# Grove_-_Tilt_Switch_v1_1.net
KiCad netlist of a schematic drawn in EAGLE
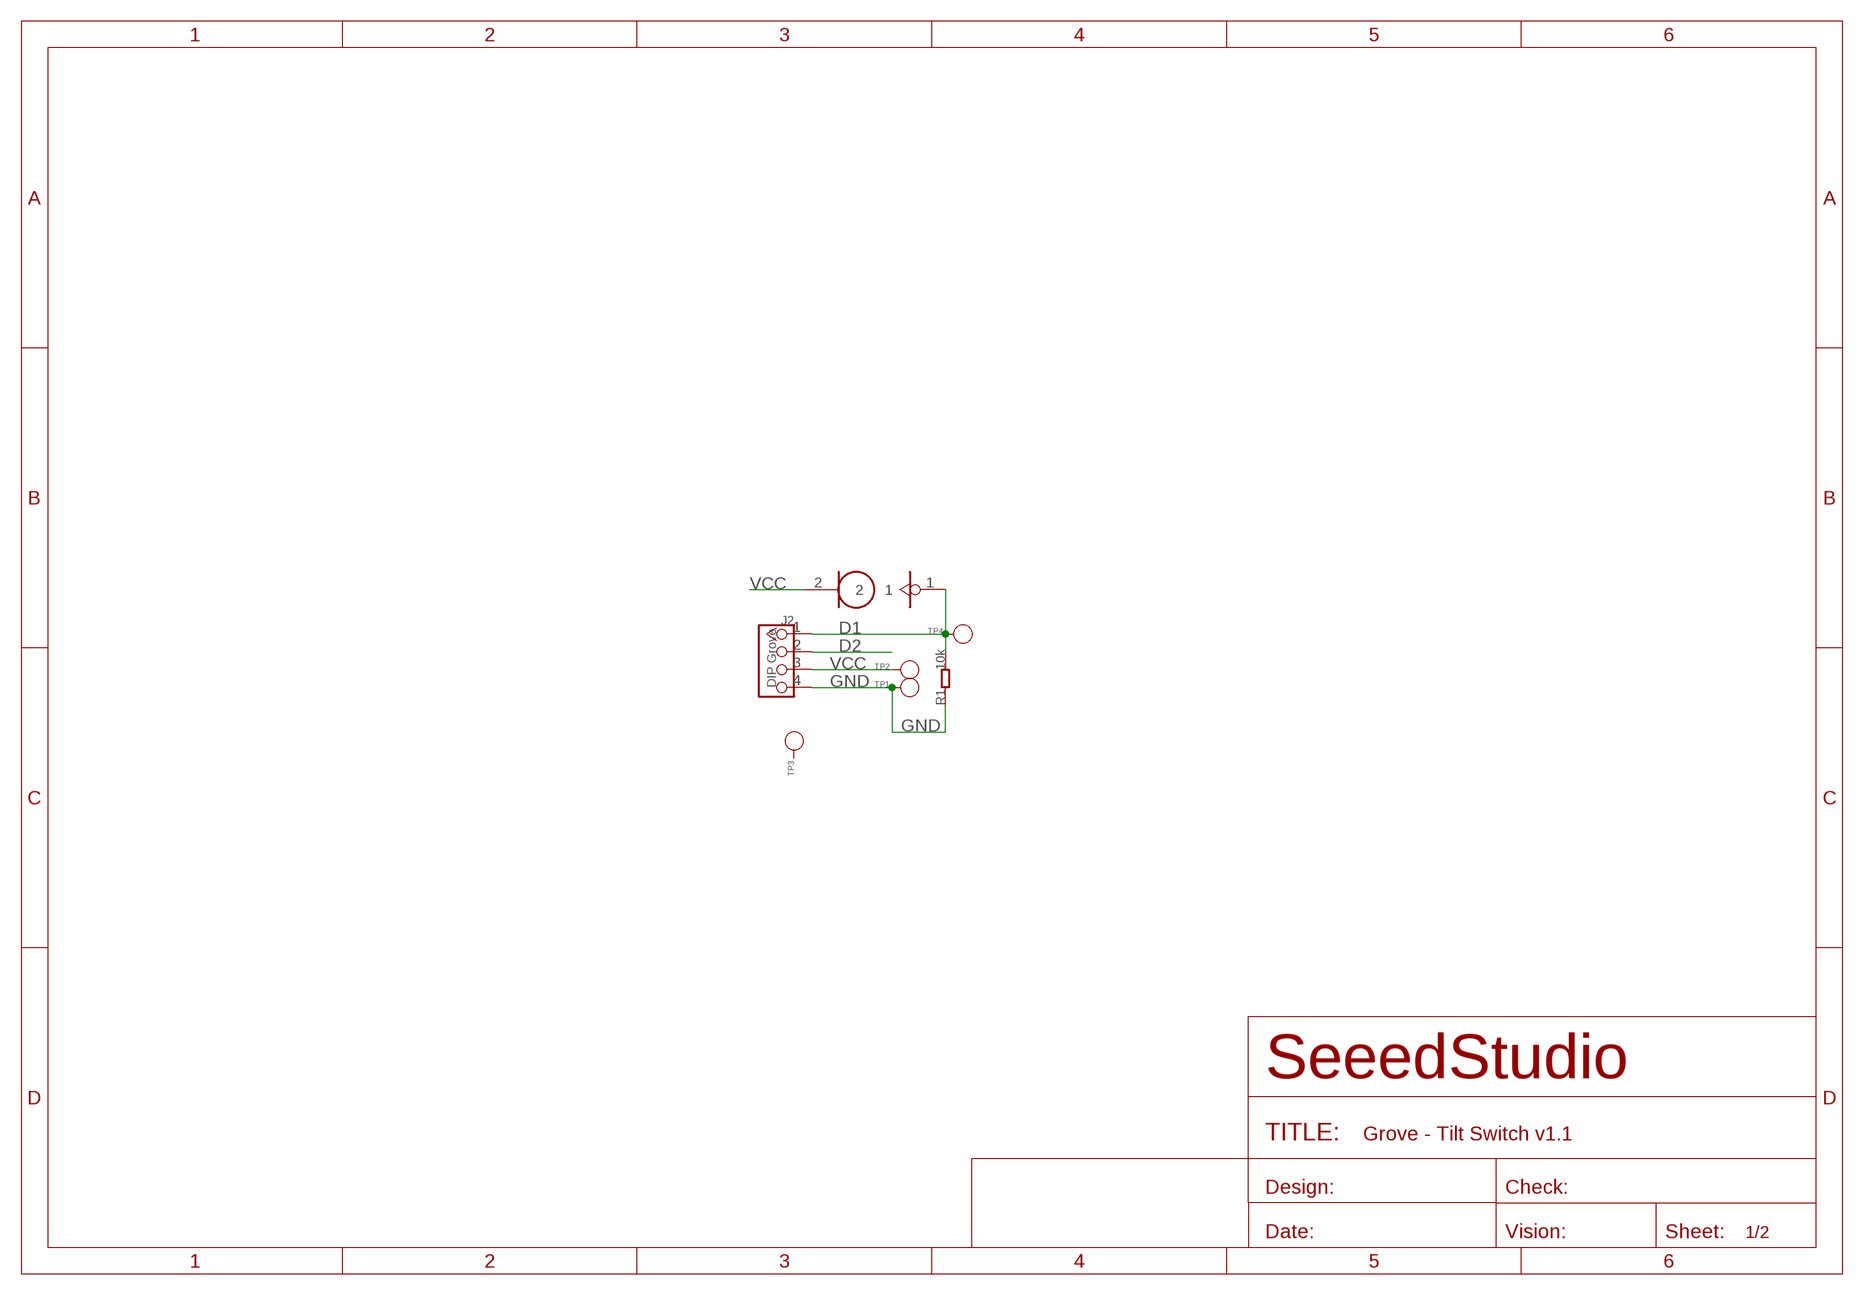
[diagram p0: schematic, sheet 1]
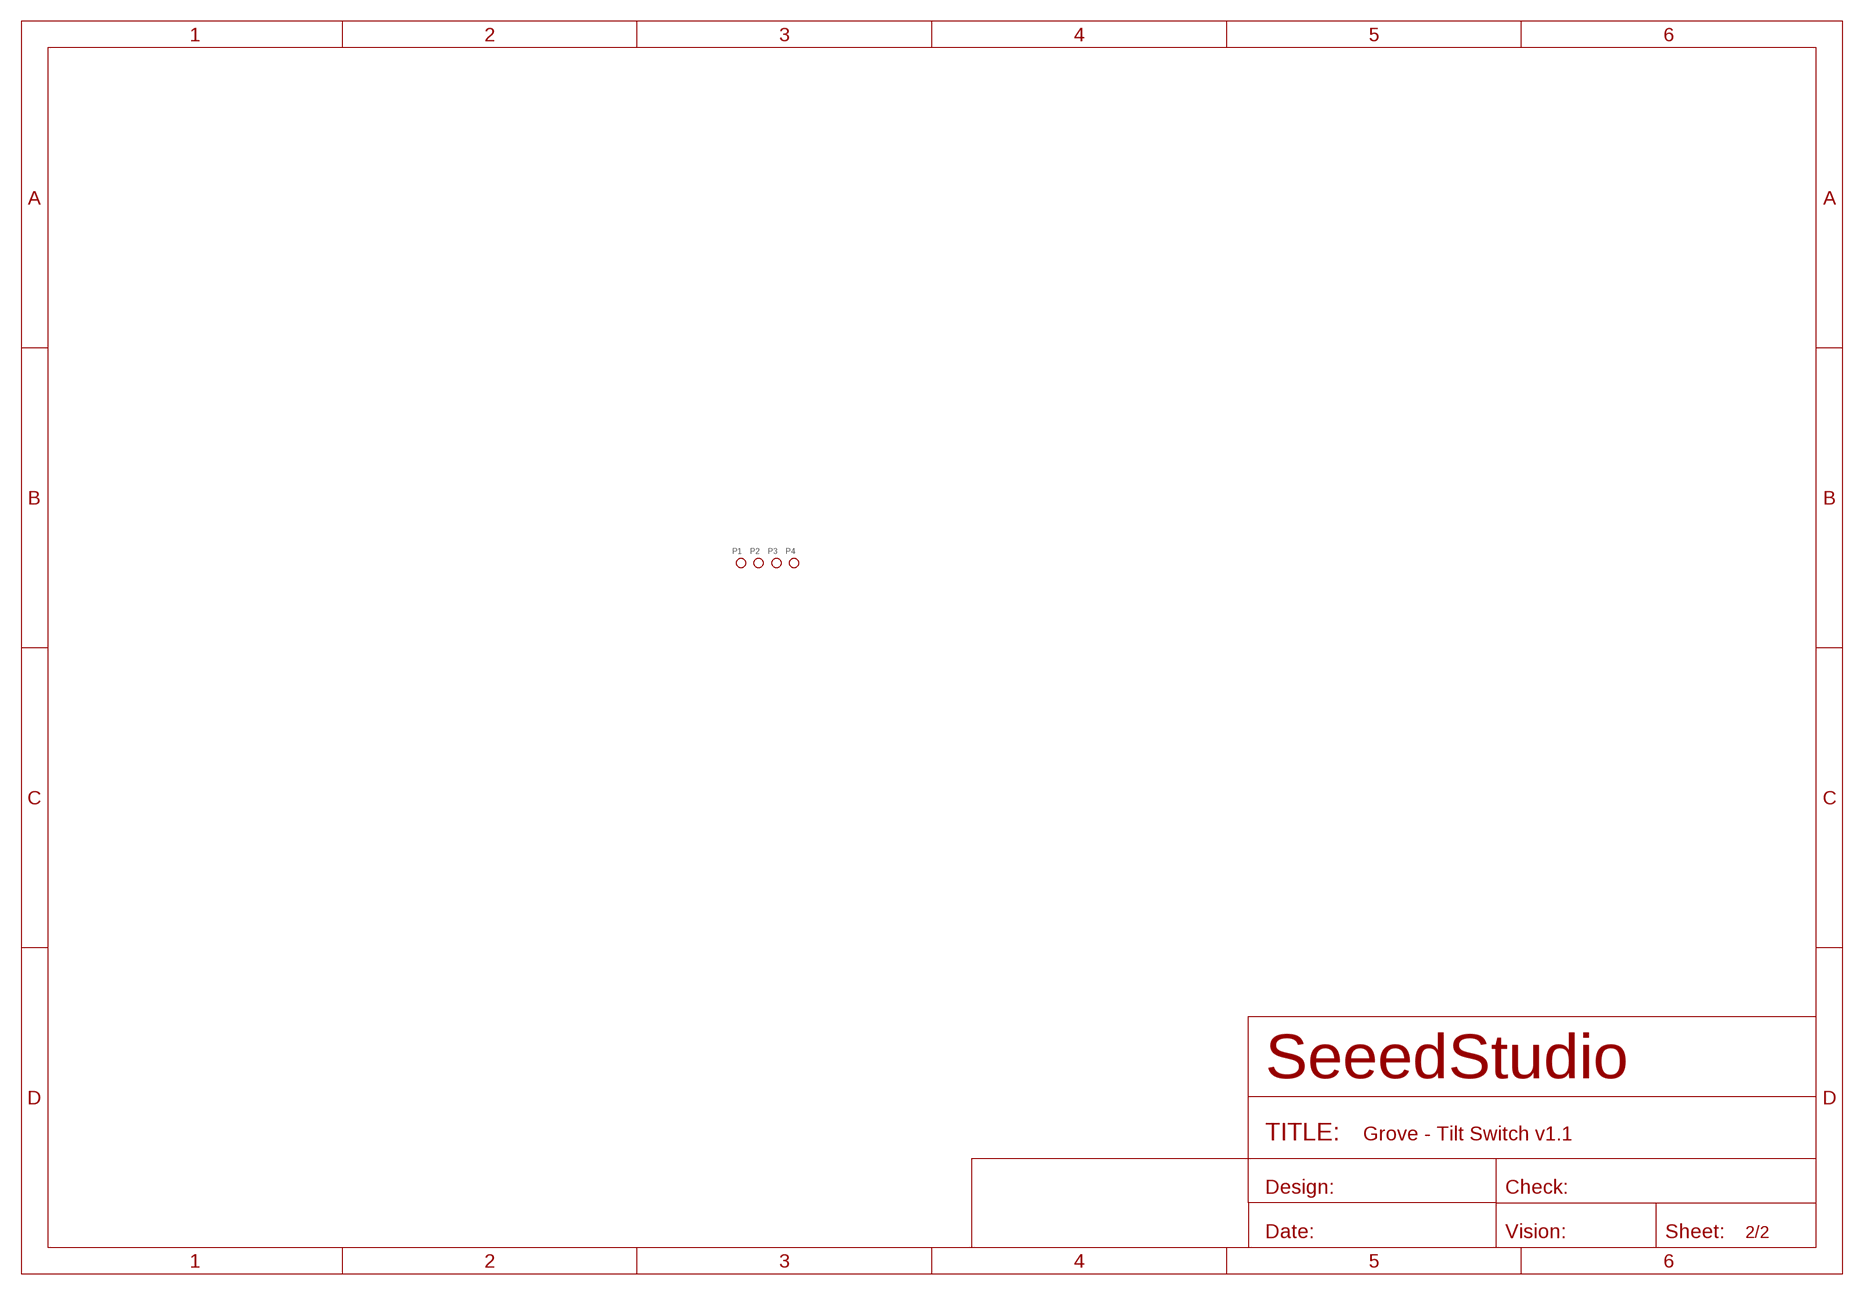
[diagram p1: schematic, sheet 2]

(export (version "E")
  (design (tool "Eeschema 10.0.6"))
  (components
    (comp (ref "J1")
      (value "TILT")
      (footprint "eagle-import:TILT")
      (libsource (lib "eagle-import") (part "TILT"))
    )
    (comp (ref "J2")
      (value "DIP Grove")
      (footprint "eagle-import:4P-2.0")
      (libsource (lib "eagle-import") (part "TWIG-4P-2.0-2.0"))
    )
    (comp (ref "R1")
      (value "10k")
      (footprint "eagle-import:0603")
      (libsource (lib "eagle-import") (part "005-R0603"))
    )
    (comp (ref "TP1")
      (value "PAD-TEST-POINT'4545'")
      (footprint "eagle-import:TP_4545")
      (fields (field (name "PARTNO") "DNP"))
      (libsource (lib "eagle-import") (part "PAD-TEST-POINT'4545'"))
    )
    (comp (ref "TP2")
      (value "PAD-TEST-POINT'4545'")
      (footprint "eagle-import:TP_4545")
      (fields (field (name "PARTNO") "DNP"))
      (libsource (lib "eagle-import") (part "PAD-TEST-POINT'4545'"))
    )
    (comp (ref "TP3")
      (value "PAD-TEST-POINT'4545'")
      (footprint "eagle-import:TP_4545")
      (fields (field (name "PARTNO") "DNP"))
      (libsource (lib "eagle-import") (part "PAD-TEST-POINT'4545'"))
    )
    (comp (ref "TP4")
      (value "PAD-TEST-POINT'4545'")
      (footprint "eagle-import:TP_4545")
      (fields (field (name "PARTNO") "DNP"))
      (libsource (lib "eagle-import") (part "PAD-TEST-POINT'4545'"))
    )
    (comp (ref "P1")
      (value "PAD-MARK")
      (footprint "eagle-import:ROUND-MARK-1.0")
      (fields (field (name "PARTNO") "DNP"))
      (libsource (lib "eagle-import") (part "PAD-MARK"))
    )
    (comp (ref "P2")
      (value "PAD-MARK")
      (footprint "eagle-import:ROUND-MARK-1.0")
      (fields (field (name "PARTNO") "DNP"))
      (libsource (lib "eagle-import") (part "PAD-MARK"))
    )
    (comp (ref "P3")
      (value "PAD-MARK")
      (footprint "eagle-import:ROUND-MARK-1.0")
      (fields (field (name "PARTNO") "DNP"))
      (libsource (lib "eagle-import") (part "PAD-MARK"))
    )
    (comp (ref "P4")
      (value "PAD-MARK")
      (footprint "eagle-import:ROUND-MARK-1.0")
      (fields (field (name "PARTNO") "DNP"))
      (libsource (lib "eagle-import") (part "PAD-MARK"))
    )
  )
  (nets
    (net (code "1") (name "D1") (class "Default")
      (node (ref "J1") (pin "1") (pinfunction "1_1") (pintype "bidirectional"))
      (node (ref "J2") (pin "1") (pinfunction "1_1") (pintype "bidirectional"))
      (node (ref "R1") (pin "2") (pinfunction "2_2") (pintype "passive"))
      (node (ref "TP4") (pin "T") (pinfunction "T_T") (pintype "bidirectional"))
    )
    (net (code "2") (name "D2") (class "Default")
      (node (ref "J2") (pin "2") (pinfunction "2_2") (pintype "bidirectional"))
    )
    (net (code "3") (name "GND") (class "Default")
      (node (ref "J2") (pin "4") (pinfunction "4_4") (pintype "bidirectional"))
      (node (ref "R1") (pin "1") (pinfunction "1_1") (pintype "passive"))
      (node (ref "TP1") (pin "T") (pinfunction "T_T") (pintype "bidirectional"))
    )
    (net (code "4") (name "VCC") (class "Default")
      (node (ref "J1") (pin "2") (pinfunction "2_2") (pintype "bidirectional"))
      (node (ref "J2") (pin "3") (pinfunction "3_3") (pintype "bidirectional"))
      (node (ref "TP2") (pin "T") (pinfunction "T_T") (pintype "bidirectional"))
    )
    (net (code "5") (name "unconnected-(TP3-PadT)") (class "Default")
      (node (ref "TP3") (pin "T") (pinfunction "T_T") (pintype "bidirectional"))
    )
  )
)
